# AccelTestJig.net
KiCad netlist of a schematic drawn in EAGLE
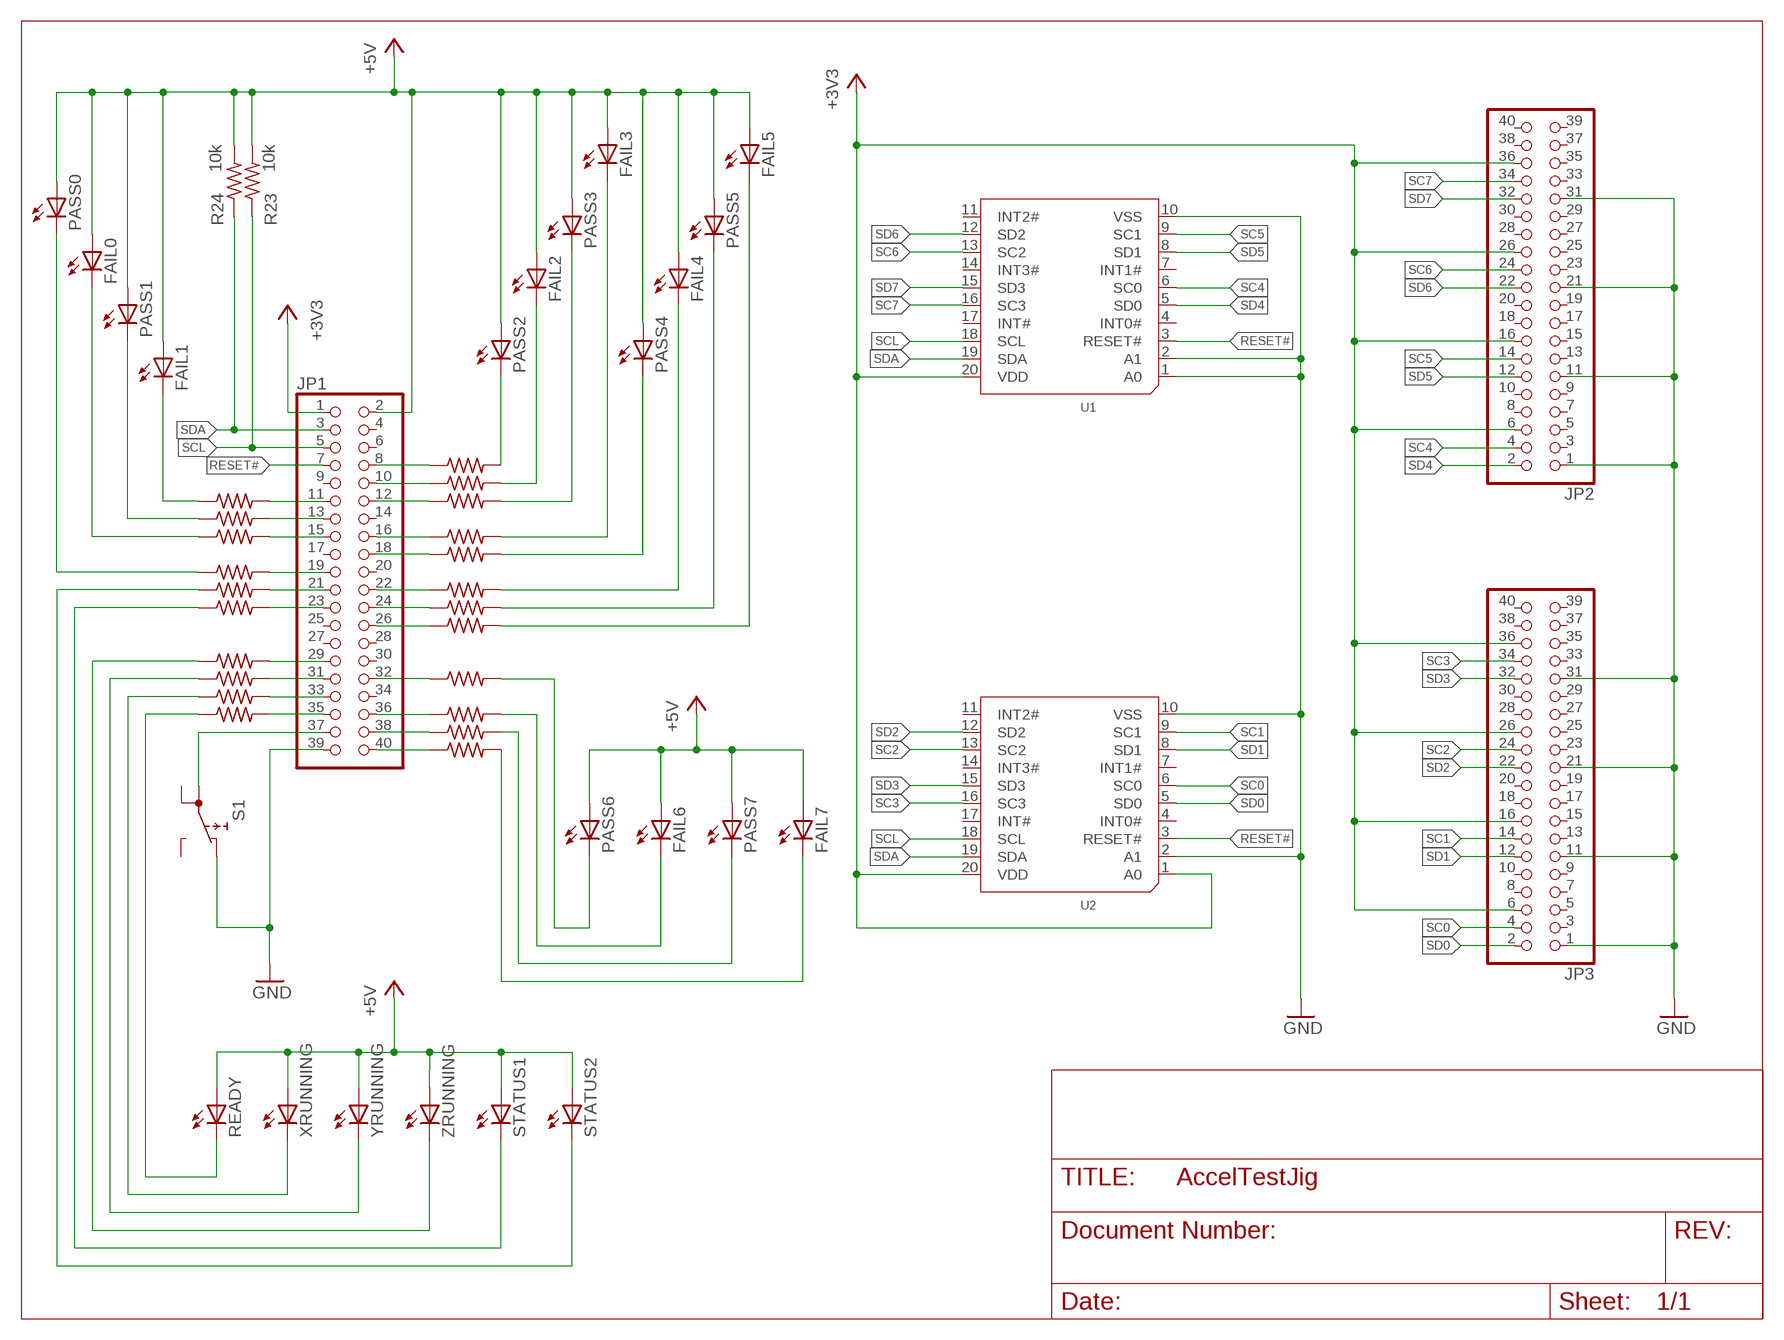
[diagram p0: schematic, sheet 1]

(export (version "E")
  (design (tool "Eeschema 10.0.6"))
  (components
    (comp (ref "FAIL0")
      (value "FAIL")
      (footprint "eagle-import:CHIPLED_0805")
      (libsource (lib "eagle-import") (part "LEDCHIPLED_0805"))
    )
    (comp (ref "FAIL1")
      (value "FAIL")
      (footprint "eagle-import:CHIPLED_0805")
      (libsource (lib "eagle-import") (part "LEDCHIPLED_0805"))
    )
    (comp (ref "FAIL2")
      (value "FAIL")
      (footprint "eagle-import:CHIPLED_0805")
      (libsource (lib "eagle-import") (part "LEDCHIPLED_0805"))
    )
    (comp (ref "FAIL3")
      (value "FAIL")
      (footprint "eagle-import:CHIPLED_0805")
      (libsource (lib "eagle-import") (part "LEDCHIPLED_0805"))
    )
    (comp (ref "FAIL4")
      (value "FAIL")
      (footprint "eagle-import:CHIPLED_0805")
      (libsource (lib "eagle-import") (part "LEDCHIPLED_0805"))
    )
    (comp (ref "FAIL5")
      (value "FAIL")
      (footprint "eagle-import:CHIPLED_0805")
      (libsource (lib "eagle-import") (part "LEDCHIPLED_0805"))
    )
    (comp (ref "FAIL6")
      (value "FAIL")
      (footprint "eagle-import:CHIPLED_0805")
      (libsource (lib "eagle-import") (part "LEDCHIPLED_0805"))
    )
    (comp (ref "FAIL7")
      (value "FAIL")
      (footprint "eagle-import:CHIPLED_0805")
      (libsource (lib "eagle-import") (part "LEDCHIPLED_0805"))
    )
    (comp (ref "JP1")
      (value "NONE")
      (footprint "eagle-import:2X20")
      (libsource (lib "eagle-import") (part "PINHD-2X20"))
    )
    (comp (ref "JP2")
      (value "NONE")
      (footprint "eagle-import:2X20-WIDE")
      (libsource (lib "eagle-import") (part "PINHD(2X20-WIDE)"))
    )
    (comp (ref "JP3")
      (value "NONE")
      (footprint "eagle-import:2X20-WIDE")
      (libsource (lib "eagle-import") (part "PINHD(2X20-WIDE)"))
    )
    (comp (ref "PASS0")
      (value "PASS")
      (footprint "eagle-import:CHIPLED_0805")
      (libsource (lib "eagle-import") (part "LEDCHIPLED_0805"))
    )
    (comp (ref "PASS1")
      (value "PASS")
      (footprint "eagle-import:CHIPLED_0805")
      (libsource (lib "eagle-import") (part "LEDCHIPLED_0805"))
    )
    (comp (ref "PASS2")
      (value "PASS")
      (footprint "eagle-import:CHIPLED_0805")
      (libsource (lib "eagle-import") (part "LEDCHIPLED_0805"))
    )
    (comp (ref "PASS3")
      (value "PASS")
      (footprint "eagle-import:CHIPLED_0805")
      (libsource (lib "eagle-import") (part "LEDCHIPLED_0805"))
    )
    (comp (ref "PASS4")
      (value "PASS")
      (footprint "eagle-import:CHIPLED_0805")
      (libsource (lib "eagle-import") (part "LEDCHIPLED_0805"))
    )
    (comp (ref "PASS5")
      (value "PASS")
      (footprint "eagle-import:CHIPLED_0805")
      (libsource (lib "eagle-import") (part "LEDCHIPLED_0805"))
    )
    (comp (ref "PASS6")
      (value "PASS")
      (footprint "eagle-import:CHIPLED_0805")
      (libsource (lib "eagle-import") (part "LEDCHIPLED_0805"))
    )
    (comp (ref "PASS7")
      (value "PASS")
      (footprint "eagle-import:CHIPLED_0805")
      (libsource (lib "eagle-import") (part "LEDCHIPLED_0805"))
    )
    (comp (ref "R1")
      (value "100")
      (footprint "eagle-import:R0805")
      (libsource (lib "eagle-import") (part "R-US_R0805"))
    )
    (comp (ref "R2")
      (value "100")
      (footprint "eagle-import:R0805")
      (libsource (lib "eagle-import") (part "R-US_R0805"))
    )
    (comp (ref "R3")
      (value "100")
      (footprint "eagle-import:R0805")
      (libsource (lib "eagle-import") (part "R-US_R0805"))
    )
    (comp (ref "R4")
      (value "100")
      (footprint "eagle-import:R0805")
      (libsource (lib "eagle-import") (part "R-US_R0805"))
    )
    (comp (ref "R5")
      (value "100")
      (footprint "eagle-import:R0805")
      (libsource (lib "eagle-import") (part "R-US_R0805"))
    )
    (comp (ref "R6")
      (value "100")
      (footprint "eagle-import:R0805")
      (libsource (lib "eagle-import") (part "R-US_R0805"))
    )
    (comp (ref "R7")
      (value "100")
      (footprint "eagle-import:R0805")
      (libsource (lib "eagle-import") (part "R-US_R0805"))
    )
    (comp (ref "R8")
      (value "100")
      (footprint "eagle-import:R0805")
      (libsource (lib "eagle-import") (part "R-US_R0805"))
    )
    (comp (ref "R9")
      (value "100")
      (footprint "eagle-import:R0805")
      (libsource (lib "eagle-import") (part "R-US_R0805"))
    )
    (comp (ref "R10")
      (value "100")
      (footprint "eagle-import:R0805")
      (libsource (lib "eagle-import") (part "R-US_R0805"))
    )
    (comp (ref "R11")
      (value "100")
      (footprint "eagle-import:R0805")
      (libsource (lib "eagle-import") (part "R-US_R0805"))
    )
    (comp (ref "R12")
      (value "100")
      (footprint "eagle-import:R0805")
      (libsource (lib "eagle-import") (part "R-US_R0805"))
    )
    (comp (ref "R13")
      (value "100")
      (footprint "eagle-import:R0805")
      (libsource (lib "eagle-import") (part "R-US_R0805"))
    )
    (comp (ref "R14")
      (value "100")
      (footprint "eagle-import:R0805")
      (libsource (lib "eagle-import") (part "R-US_R0805"))
    )
    (comp (ref "R15")
      (value "100")
      (footprint "eagle-import:R0805")
      (libsource (lib "eagle-import") (part "R-US_R0805"))
    )
    (comp (ref "R16")
      (value "100")
      (footprint "eagle-import:R0805")
      (libsource (lib "eagle-import") (part "R-US_R0805"))
    )
    (comp (ref "R17")
      (value "100")
      (footprint "eagle-import:R0805")
      (libsource (lib "eagle-import") (part "R-US_R0805"))
    )
    (comp (ref "R18")
      (value "100")
      (footprint "eagle-import:R0805")
      (libsource (lib "eagle-import") (part "R-US_R0805"))
    )
    (comp (ref "R19")
      (value "100")
      (footprint "eagle-import:R0805")
      (libsource (lib "eagle-import") (part "R-US_R0805"))
    )
    (comp (ref "R20")
      (value "100")
      (footprint "eagle-import:R0805")
      (libsource (lib "eagle-import") (part "R-US_R0805"))
    )
    (comp (ref "R21")
      (value "100")
      (footprint "eagle-import:R0805")
      (libsource (lib "eagle-import") (part "R-US_R0805"))
    )
    (comp (ref "R22")
      (value "100")
      (footprint "eagle-import:R0805")
      (libsource (lib "eagle-import") (part "R-US_R0805"))
    )
    (comp (ref "R23")
      (value "10k")
      (footprint "eagle-import:R0805")
      (libsource (lib "eagle-import") (part "R-US_R0805"))
    )
    (comp (ref "R24")
      (value "10k")
      (footprint "eagle-import:R0805")
      (libsource (lib "eagle-import") (part "R-US_R0805"))
    )
    (comp (ref "READY")
      (value "READY")
      (footprint "eagle-import:CHIPLED_0805")
      (libsource (lib "eagle-import") (part "LEDCHIPLED_0805"))
    )
    (comp (ref "S1")
      (value "START")
      (footprint "eagle-import:6X6SMD")
      (libsource (lib "eagle-import") (part "PUSHBUTTON(6X6SMD)01"))
    )
    (comp (ref "STATUS1")
      (value "NONE")
      (footprint "eagle-import:CHIPLED_0805")
      (libsource (lib "eagle-import") (part "LEDCHIPLED_0805"))
    )
    (comp (ref "STATUS2")
      (value "NONE")
      (footprint "eagle-import:CHIPLED_0805")
      (libsource (lib "eagle-import") (part "LEDCHIPLED_0805"))
    )
    (comp (ref "U1")
      (value "NONE")
      (footprint "eagle-import:SOIC20")
      (libsource (lib "eagle-import") (part "PCA9545(SOIC20)"))
    )
    (comp (ref "U2")
      (value "NONE")
      (footprint "eagle-import:SOIC20")
      (libsource (lib "eagle-import") (part "PCA9545(SOIC20)"))
    )
    (comp (ref "XRUNNING")
      (value "TESTING X")
      (footprint "eagle-import:CHIPLED_0805")
      (libsource (lib "eagle-import") (part "LEDCHIPLED_0805"))
    )
    (comp (ref "YRUNNING")
      (value "TESTING Y")
      (footprint "eagle-import:CHIPLED_0805")
      (libsource (lib "eagle-import") (part "LEDCHIPLED_0805"))
    )
    (comp (ref "ZRUNNING")
      (value "TESTING Z")
      (footprint "eagle-import:CHIPLED_0805")
      (libsource (lib "eagle-import") (part "LEDCHIPLED_0805"))
    )
  )
  (nets
    (net (code "1") (name "+3V3") (class "Default")
      (node (ref "JP1") (pin "1") (pinfunction "1_1") (pintype "passive"))
      (node (ref "JP2") (pin "16") (pinfunction "16_16") (pintype "passive"))
      (node (ref "JP2") (pin "26") (pinfunction "26_26") (pintype "passive"))
      (node (ref "JP2") (pin "36") (pinfunction "36_36") (pintype "passive"))
      (node (ref "JP2") (pin "6") (pinfunction "6_6") (pintype "passive"))
      (node (ref "JP3") (pin "16") (pinfunction "16_16") (pintype "passive"))
      (node (ref "JP3") (pin "26") (pinfunction "26_26") (pintype "passive"))
      (node (ref "JP3") (pin "36") (pinfunction "36_36") (pintype "passive"))
      (node (ref "JP3") (pin "6") (pinfunction "6_6") (pintype "passive"))
      (node (ref "U1") (pin "20") (pinfunction "VDD_20") (pintype "bidirectional"))
      (node (ref "U2") (pin "1") (pinfunction "A0_1") (pintype "bidirectional"))
      (node (ref "U2") (pin "20") (pinfunction "VDD_20") (pintype "bidirectional"))
    )
    (net (code "2") (name "+5V") (class "Default")
      (node (ref "FAIL0") (pin "A") (pinfunction "A_A") (pintype "passive"))
      (node (ref "FAIL1") (pin "A") (pinfunction "A_A") (pintype "passive"))
      (node (ref "FAIL2") (pin "A") (pinfunction "A_A") (pintype "passive"))
      (node (ref "FAIL3") (pin "A") (pinfunction "A_A") (pintype "passive"))
      (node (ref "FAIL4") (pin "A") (pinfunction "A_A") (pintype "passive"))
      (node (ref "FAIL5") (pin "A") (pinfunction "A_A") (pintype "passive"))
      (node (ref "FAIL6") (pin "A") (pinfunction "A_A") (pintype "passive"))
      (node (ref "FAIL7") (pin "A") (pinfunction "A_A") (pintype "passive"))
      (node (ref "JP1") (pin "2") (pinfunction "2_2") (pintype "passive"))
      (node (ref "PASS0") (pin "A") (pinfunction "A_A") (pintype "passive"))
      (node (ref "PASS1") (pin "A") (pinfunction "A_A") (pintype "passive"))
      (node (ref "PASS2") (pin "A") (pinfunction "A_A") (pintype "passive"))
      (node (ref "PASS3") (pin "A") (pinfunction "A_A") (pintype "passive"))
      (node (ref "PASS4") (pin "A") (pinfunction "A_A") (pintype "passive"))
      (node (ref "PASS5") (pin "A") (pinfunction "A_A") (pintype "passive"))
      (node (ref "PASS6") (pin "A") (pinfunction "A_A") (pintype "passive"))
      (node (ref "PASS7") (pin "A") (pinfunction "A_A") (pintype "passive"))
      (node (ref "R23") (pin "2") (pinfunction "2_2") (pintype "passive"))
      (node (ref "R24") (pin "2") (pinfunction "2_2") (pintype "passive"))
      (node (ref "READY") (pin "A") (pinfunction "A_A") (pintype "passive"))
      (node (ref "STATUS1") (pin "A") (pinfunction "A_A") (pintype "passive"))
      (node (ref "STATUS2") (pin "A") (pinfunction "A_A") (pintype "passive"))
      (node (ref "XRUNNING") (pin "A") (pinfunction "A_A") (pintype "passive"))
      (node (ref "YRUNNING") (pin "A") (pinfunction "A_A") (pintype "passive"))
      (node (ref "ZRUNNING") (pin "A") (pinfunction "A_A") (pintype "passive"))
    )
    (net (code "3") (name "GND") (class "Default")
      (node (ref "JP1") (pin "39") (pinfunction "39_39") (pintype "passive"))
      (node (ref "JP2") (pin "1") (pinfunction "1_1") (pintype "passive"))
      (node (ref "JP2") (pin "11") (pinfunction "11_11") (pintype "passive"))
      (node (ref "JP2") (pin "21") (pinfunction "21_21") (pintype "passive"))
      (node (ref "JP2") (pin "31") (pinfunction "31_31") (pintype "passive"))
      (node (ref "JP3") (pin "1") (pinfunction "1_1") (pintype "passive"))
      (node (ref "JP3") (pin "11") (pinfunction "11_11") (pintype "passive"))
      (node (ref "JP3") (pin "21") (pinfunction "21_21") (pintype "passive"))
      (node (ref "JP3") (pin "31") (pinfunction "31_31") (pintype "passive"))
      (node (ref "S1") (pin "P$2") (pinfunction "2_P$2") (pintype "passive"))
      (node (ref "U1") (pin "1") (pinfunction "A0_1") (pintype "bidirectional"))
      (node (ref "U1") (pin "10") (pinfunction "VSS_10") (pintype "bidirectional"))
      (node (ref "U1") (pin "2") (pinfunction "A1_2") (pintype "bidirectional"))
      (node (ref "U2") (pin "10") (pinfunction "VSS_10") (pintype "bidirectional"))
      (node (ref "U2") (pin "2") (pinfunction "A1_2") (pintype "bidirectional"))
    )
    (net (code "4") (name "Net-(FAIL0-PadC)") (class "Default")
      (node (ref "FAIL0") (pin "C") (pinfunction "C_C") (pintype "passive"))
      (node (ref "R18") (pin "1") (pinfunction "1_1") (pintype "passive"))
    )
    (net (code "5") (name "Net-(FAIL1-PadC)") (class "Default")
      (node (ref "FAIL1") (pin "C") (pinfunction "C_C") (pintype "passive"))
      (node (ref "R16") (pin "1") (pinfunction "1_1") (pintype "passive"))
    )
    (net (code "6") (name "Net-(FAIL2-PadC)") (class "Default")
      (node (ref "FAIL2") (pin "C") (pinfunction "C_C") (pintype "passive"))
      (node (ref "R2") (pin "2") (pinfunction "2_2") (pintype "passive"))
    )
    (net (code "7") (name "Net-(FAIL3-PadC)") (class "Default")
      (node (ref "FAIL3") (pin "C") (pinfunction "C_C") (pintype "passive"))
      (node (ref "R3") (pin "2") (pinfunction "2_2") (pintype "passive"))
    )
    (net (code "8") (name "Net-(FAIL4-PadC)") (class "Default")
      (node (ref "FAIL4") (pin "C") (pinfunction "C_C") (pintype "passive"))
      (node (ref "R5") (pin "2") (pinfunction "2_2") (pintype "passive"))
    )
    (net (code "9") (name "Net-(FAIL5-PadC)") (class "Default")
      (node (ref "FAIL5") (pin "C") (pinfunction "C_C") (pintype "passive"))
      (node (ref "R7") (pin "2") (pinfunction "2_2") (pintype "passive"))
    )
    (net (code "10") (name "Net-(FAIL6-PadC)") (class "Default")
      (node (ref "FAIL6") (pin "C") (pinfunction "C_C") (pintype "passive"))
      (node (ref "R9") (pin "2") (pinfunction "2_2") (pintype "passive"))
    )
    (net (code "11") (name "Net-(FAIL7-PadC)") (class "Default")
      (node (ref "FAIL7") (pin "C") (pinfunction "C_C") (pintype "passive"))
      (node (ref "R15") (pin "2") (pinfunction "2_2") (pintype "passive"))
    )
    (net (code "12") (name "Net-(JP1-Pad8)") (class "Default")
      (node (ref "JP1") (pin "8") (pinfunction "8_8") (pintype "passive"))
      (node (ref "R1") (pin "1") (pinfunction "1_1") (pintype "passive"))
    )
    (net (code "13") (name "Net-(JP1-Pad10)") (class "Default")
      (node (ref "JP1") (pin "10") (pinfunction "10_10") (pintype "passive"))
      (node (ref "R2") (pin "1") (pinfunction "1_1") (pintype "passive"))
    )
    (net (code "14") (name "Net-(JP1-Pad11)") (class "Default")
      (node (ref "JP1") (pin "11") (pinfunction "11_11") (pintype "passive"))
      (node (ref "R16") (pin "2") (pinfunction "2_2") (pintype "passive"))
    )
    (net (code "15") (name "Net-(JP1-Pad12)") (class "Default")
      (node (ref "JP1") (pin "12") (pinfunction "12_12") (pintype "passive"))
      (node (ref "R14") (pin "1") (pinfunction "1_1") (pintype "passive"))
    )
    (net (code "16") (name "Net-(JP1-Pad13)") (class "Default")
      (node (ref "JP1") (pin "13") (pinfunction "13_13") (pintype "passive"))
      (node (ref "R17") (pin "2") (pinfunction "2_2") (pintype "passive"))
    )
    (net (code "17") (name "Net-(JP1-Pad15)") (class "Default")
      (node (ref "JP1") (pin "15") (pinfunction "15_15") (pintype "passive"))
      (node (ref "R18") (pin "2") (pinfunction "2_2") (pintype "passive"))
    )
    (net (code "18") (name "Net-(JP1-Pad16)") (class "Default")
      (node (ref "JP1") (pin "16") (pinfunction "16_16") (pintype "passive"))
      (node (ref "R3") (pin "1") (pinfunction "1_1") (pintype "passive"))
    )
    (net (code "19") (name "Net-(JP1-Pad18)") (class "Default")
      (node (ref "JP1") (pin "18") (pinfunction "18_18") (pintype "passive"))
      (node (ref "R4") (pin "1") (pinfunction "1_1") (pintype "passive"))
    )
    (net (code "20") (name "Net-(JP1-Pad19)") (class "Default")
      (node (ref "JP1") (pin "19") (pinfunction "19_19") (pintype "passive"))
      (node (ref "R19") (pin "2") (pinfunction "2_2") (pintype "passive"))
    )
    (net (code "21") (name "Net-(JP1-Pad21)") (class "Default")
      (node (ref "JP1") (pin "21") (pinfunction "21_21") (pintype "passive"))
      (node (ref "R20") (pin "2") (pinfunction "2_2") (pintype "passive"))
    )
    (net (code "22") (name "Net-(JP1-Pad22)") (class "Default")
      (node (ref "JP1") (pin "22") (pinfunction "22_22") (pintype "passive"))
      (node (ref "R5") (pin "1") (pinfunction "1_1") (pintype "passive"))
    )
    (net (code "23") (name "Net-(JP1-Pad23)") (class "Default")
      (node (ref "JP1") (pin "23") (pinfunction "23_23") (pintype "passive"))
      (node (ref "R11") (pin "2") (pinfunction "2_2") (pintype "passive"))
    )
    (net (code "24") (name "Net-(JP1-Pad24)") (class "Default")
      (node (ref "JP1") (pin "24") (pinfunction "24_24") (pintype "passive"))
      (node (ref "R6") (pin "1") (pinfunction "1_1") (pintype "passive"))
    )
    (net (code "25") (name "Net-(JP1-Pad26)") (class "Default")
      (node (ref "JP1") (pin "26") (pinfunction "26_26") (pintype "passive"))
      (node (ref "R7") (pin "1") (pinfunction "1_1") (pintype "passive"))
    )
    (net (code "26") (name "Net-(JP1-Pad29)") (class "Default")
      (node (ref "JP1") (pin "29") (pinfunction "29_29") (pintype "passive"))
      (node (ref "R12") (pin "2") (pinfunction "2_2") (pintype "passive"))
    )
    (net (code "27") (name "Net-(JP1-Pad31)") (class "Default")
      (node (ref "JP1") (pin "31") (pinfunction "31_31") (pintype "passive"))
      (node (ref "R13") (pin "2") (pinfunction "2_2") (pintype "passive"))
    )
    (net (code "28") (name "Net-(JP1-Pad32)") (class "Default")
      (node (ref "JP1") (pin "32") (pinfunction "32_32") (pintype "passive"))
      (node (ref "R8") (pin "1") (pinfunction "1_1") (pintype "passive"))
    )
    (net (code "29") (name "Net-(JP1-Pad33)") (class "Default")
      (node (ref "JP1") (pin "33") (pinfunction "33_33") (pintype "passive"))
      (node (ref "R21") (pin "2") (pinfunction "2_2") (pintype "passive"))
    )
    (net (code "30") (name "Net-(JP1-Pad35)") (class "Default")
      (node (ref "JP1") (pin "35") (pinfunction "35_35") (pintype "passive"))
      (node (ref "R22") (pin "2") (pinfunction "2_2") (pintype "passive"))
    )
    (net (code "31") (name "Net-(JP1-Pad36)") (class "Default")
      (node (ref "JP1") (pin "36") (pinfunction "36_36") (pintype "passive"))
      (node (ref "R9") (pin "1") (pinfunction "1_1") (pintype "passive"))
    )
    (net (code "32") (name "Net-(JP1-Pad38)") (class "Default")
      (node (ref "JP1") (pin "38") (pinfunction "38_38") (pintype "passive"))
      (node (ref "R10") (pin "1") (pinfunction "1_1") (pintype "passive"))
    )
    (net (code "33") (name "Net-(JP1-Pad40)") (class "Default")
      (node (ref "JP1") (pin "40") (pinfunction "40_40") (pintype "passive"))
      (node (ref "R15") (pin "1") (pinfunction "1_1") (pintype "passive"))
    )
    (net (code "34") (name "Net-(PASS0-PadC)") (class "Default")
      (node (ref "PASS0") (pin "C") (pinfunction "C_C") (pintype "passive"))
      (node (ref "R19") (pin "1") (pinfunction "1_1") (pintype "passive"))
    )
    (net (code "35") (name "Net-(PASS1-PadC)") (class "Default")
      (node (ref "PASS1") (pin "C") (pinfunction "C_C") (pintype "passive"))
      (node (ref "R17") (pin "1") (pinfunction "1_1") (pintype "passive"))
    )
    (net (code "36") (name "Net-(PASS2-PadC)") (class "Default")
      (node (ref "PASS2") (pin "C") (pinfunction "C_C") (pintype "passive"))
      (node (ref "R1") (pin "2") (pinfunction "2_2") (pintype "passive"))
    )
    (net (code "37") (name "Net-(PASS3-PadC)") (class "Default")
      (node (ref "PASS3") (pin "C") (pinfunction "C_C") (pintype "passive"))
      (node (ref "R14") (pin "2") (pinfunction "2_2") (pintype "passive"))
    )
    (net (code "38") (name "Net-(PASS4-PadC)") (class "Default")
      (node (ref "PASS4") (pin "C") (pinfunction "C_C") (pintype "passive"))
      (node (ref "R4") (pin "2") (pinfunction "2_2") (pintype "passive"))
    )
    (net (code "39") (name "Net-(PASS5-PadC)") (class "Default")
      (node (ref "PASS5") (pin "C") (pinfunction "C_C") (pintype "passive"))
      (node (ref "R6") (pin "2") (pinfunction "2_2") (pintype "passive"))
    )
    (net (code "40") (name "Net-(PASS6-PadC)") (class "Default")
      (node (ref "PASS6") (pin "C") (pinfunction "C_C") (pintype "passive"))
      (node (ref "R8") (pin "2") (pinfunction "2_2") (pintype "passive"))
    )
    (net (code "41") (name "Net-(PASS7-PadC)") (class "Default")
      (node (ref "PASS7") (pin "C") (pinfunction "C_C") (pintype "passive"))
      (node (ref "R10") (pin "2") (pinfunction "2_2") (pintype "passive"))
    )
    (net (code "42") (name "Net-(R11-Pad1)") (class "Default")
      (node (ref "R11") (pin "1") (pinfunction "1_1") (pintype "passive"))
      (node (ref "STATUS1") (pin "C") (pinfunction "C_C") (pintype "passive"))
    )
    (net (code "43") (name "Net-(R12-Pad1)") (class "Default")
      (node (ref "R12") (pin "1") (pinfunction "1_1") (pintype "passive"))
      (node (ref "ZRUNNING") (pin "C") (pinfunction "C_C") (pintype "passive"))
    )
    (net (code "44") (name "Net-(R13-Pad1)") (class "Default")
      (node (ref "R13") (pin "1") (pinfunction "1_1") (pintype "passive"))
      (node (ref "YRUNNING") (pin "C") (pinfunction "C_C") (pintype "passive"))
    )
    (net (code "45") (name "Net-(R20-Pad1)") (class "Default")
      (node (ref "R20") (pin "1") (pinfunction "1_1") (pintype "passive"))
      (node (ref "STATUS2") (pin "C") (pinfunction "C_C") (pintype "passive"))
    )
    (net (code "46") (name "Net-(R21-Pad1)") (class "Default")
      (node (ref "R21") (pin "1") (pinfunction "1_1") (pintype "passive"))
      (node (ref "XRUNNING") (pin "C") (pinfunction "C_C") (pintype "passive"))
    )
    (net (code "47") (name "Net-(R22-Pad1)") (class "Default")
      (node (ref "R22") (pin "1") (pinfunction "1_1") (pintype "passive"))
      (node (ref "READY") (pin "C") (pinfunction "C_C") (pintype "passive"))
    )
    (net (code "48") (name "Net-(S1-1)") (class "Default")
      (node (ref "JP1") (pin "37") (pinfunction "37_37") (pintype "passive"))
      (node (ref "S1") (pin "P$1") (pinfunction "1_P$1") (pintype "passive"))
    )
    (net (code "49") (name "RESET#") (class "Default")
      (node (ref "JP1") (pin "7") (pinfunction "7_7") (pintype "passive"))
      (node (ref "U1") (pin "3") (pinfunction "RESET#_3") (pintype "bidirectional"))
      (node (ref "U2") (pin "3") (pinfunction "RESET#_3") (pintype "bidirectional"))
    )
    (net (code "50") (name "SC0") (class "Default")
      (node (ref "JP3") (pin "4") (pinfunction "4_4") (pintype "passive"))
      (node (ref "U2") (pin "6") (pinfunction "SC0_6") (pintype "bidirectional"))
    )
    (net (code "51") (name "SC1") (class "Default")
      (node (ref "JP3") (pin "14") (pinfunction "14_14") (pintype "passive"))
      (node (ref "U2") (pin "9") (pinfunction "SC1_9") (pintype "bidirectional"))
    )
    (net (code "52") (name "SC2") (class "Default")
      (node (ref "JP3") (pin "24") (pinfunction "24_24") (pintype "passive"))
      (node (ref "U2") (pin "13") (pinfunction "SC2_13") (pintype "bidirectional"))
    )
    (net (code "53") (name "SC3") (class "Default")
      (node (ref "JP3") (pin "34") (pinfunction "34_34") (pintype "passive"))
      (node (ref "U2") (pin "16") (pinfunction "SC3_16") (pintype "bidirectional"))
    )
    (net (code "54") (name "SC4") (class "Default")
      (node (ref "JP2") (pin "4") (pinfunction "4_4") (pintype "passive"))
      (node (ref "U1") (pin "6") (pinfunction "SC0_6") (pintype "bidirectional"))
    )
    (net (code "55") (name "SC5") (class "Default")
      (node (ref "JP2") (pin "14") (pinfunction "14_14") (pintype "passive"))
      (node (ref "U1") (pin "9") (pinfunction "SC1_9") (pintype "bidirectional"))
    )
    (net (code "56") (name "SC6") (class "Default")
      (node (ref "JP2") (pin "24") (pinfunction "24_24") (pintype "passive"))
      (node (ref "U1") (pin "13") (pinfunction "SC2_13") (pintype "bidirectional"))
    )
    (net (code "57") (name "SC7") (class "Default")
      (node (ref "JP2") (pin "34") (pinfunction "34_34") (pintype "passive"))
      (node (ref "U1") (pin "16") (pinfunction "SC3_16") (pintype "bidirectional"))
    )
    (net (code "58") (name "SCL") (class "Default")
      (node (ref "JP1") (pin "5") (pinfunction "5_5") (pintype "passive"))
      (node (ref "R23") (pin "1") (pinfunction "1_1") (pintype "passive"))
      (node (ref "U1") (pin "18") (pinfunction "SCL_18") (pintype "bidirectional"))
      (node (ref "U2") (pin "18") (pinfunction "SCL_18") (pintype "bidirectional"))
    )
    (net (code "59") (name "SD0") (class "Default")
      (node (ref "JP3") (pin "2") (pinfunction "2_2") (pintype "passive"))
      (node (ref "U2") (pin "5") (pinfunction "SD0_5") (pintype "bidirectional"))
    )
    (net (code "60") (name "SD1") (class "Default")
      (node (ref "JP3") (pin "12") (pinfunction "12_12") (pintype "passive"))
      (node (ref "U2") (pin "8") (pinfunction "SD1_8") (pintype "bidirectional"))
    )
    (net (code "61") (name "SD2") (class "Default")
      (node (ref "JP3") (pin "22") (pinfunction "22_22") (pintype "passive"))
      (node (ref "U2") (pin "12") (pinfunction "SD2_12") (pintype "bidirectional"))
    )
    (net (code "62") (name "SD3") (class "Default")
      (node (ref "JP3") (pin "32") (pinfunction "32_32") (pintype "passive"))
      (node (ref "U2") (pin "15") (pinfunction "SD3_15") (pintype "bidirectional"))
    )
    (net (code "63") (name "SD4") (class "Default")
      (node (ref "JP2") (pin "2") (pinfunction "2_2") (pintype "passive"))
      (node (ref "U1") (pin "5") (pinfunction "SD0_5") (pintype "bidirectional"))
    )
    (net (code "64") (name "SD5") (class "Default")
      (node (ref "JP2") (pin "12") (pinfunction "12_12") (pintype "passive"))
      (node (ref "U1") (pin "8") (pinfunction "SD1_8") (pintype "bidirectional"))
    )
    (net (code "65") (name "SD6") (class "Default")
      (node (ref "JP2") (pin "22") (pinfunction "22_22") (pintype "passive"))
      (node (ref "U1") (pin "12") (pinfunction "SD2_12") (pintype "bidirectional"))
    )
    (net (code "66") (name "SD7") (class "Default")
      (node (ref "JP2") (pin "32") (pinfunction "32_32") (pintype "passive"))
      (node (ref "U1") (pin "15") (pinfunction "SD3_15") (pintype "bidirectional"))
    )
    (net (code "67") (name "SDA") (class "Default")
      (node (ref "JP1") (pin "3") (pinfunction "3_3") (pintype "passive"))
      (node (ref "R24") (pin "1") (pinfunction "1_1") (pintype "passive"))
      (node (ref "U1") (pin "19") (pinfunction "SDA_19") (pintype "bidirectional"))
      (node (ref "U2") (pin "19") (pinfunction "SDA_19") (pintype "bidirectional"))
    )
    (net (code "68") (name "unconnected-(JP1-Pad4)") (class "Default")
      (node (ref "JP1") (pin "4") (pinfunction "4_4") (pintype "passive"))
    )
    (net (code "69") (name "unconnected-(JP1-Pad6)") (class "Default")
      (node (ref "JP1") (pin "6") (pinfunction "6_6") (pintype "passive"))
    )
    (net (code "70") (name "unconnected-(JP1-Pad9)") (class "Default")
      (node (ref "JP1") (pin "9") (pinfunction "9_9") (pintype "passive"))
    )
    (net (code "71") (name "unconnected-(JP1-Pad14)") (class "Default")
      (node (ref "JP1") (pin "14") (pinfunction "14_14") (pintype "passive"))
    )
    (net (code "72") (name "unconnected-(JP1-Pad17)") (class "Default")
      (node (ref "JP1") (pin "17") (pinfunction "17_17") (pintype "passive"))
    )
    (net (code "73") (name "unconnected-(JP1-Pad20)") (class "Default")
      (node (ref "JP1") (pin "20") (pinfunction "20_20") (pintype "passive"))
    )
    (net (code "74") (name "unconnected-(JP1-Pad25)") (class "Default")
      (node (ref "JP1") (pin "25") (pinfunction "25_25") (pintype "passive"))
    )
    (net (code "75") (name "unconnected-(JP1-Pad27)") (class "Default")
      (node (ref "JP1") (pin "27") (pinfunction "27_27") (pintype "passive"))
    )
    (net (code "76") (name "unconnected-(JP1-Pad28)") (class "Default")
      (node (ref "JP1") (pin "28") (pinfunction "28_28") (pintype "passive"))
    )
    (net (code "77") (name "unconnected-(JP1-Pad30)") (class "Default")
      (node (ref "JP1") (pin "30") (pinfunction "30_30") (pintype "passive"))
    )
    (net (code "78") (name "unconnected-(JP1-Pad34)") (class "Default")
      (node (ref "JP1") (pin "34") (pinfunction "34_34") (pintype "passive"))
    )
    (net (code "79") (name "unconnected-(JP2-Pad3)") (class "Default")
      (node (ref "JP2") (pin "3") (pinfunction "3_3") (pintype "passive"))
    )
    (net (code "80") (name "unconnected-(JP2-Pad5)") (class "Default")
      (node (ref "JP2") (pin "5") (pinfunction "5_5") (pintype "passive"))
    )
    (net (code "81") (name "unconnected-(JP2-Pad7)") (class "Default")
      (node (ref "JP2") (pin "7") (pinfunction "7_7") (pintype "passive"))
    )
    (net (code "82") (name "unconnected-(JP2-Pad8)") (class "Default")
      (node (ref "JP2") (pin "8") (pinfunction "8_8") (pintype "passive"))
    )
    (net (code "83") (name "unconnected-(JP2-Pad9)") (class "Default")
      (node (ref "JP2") (pin "9") (pinfunction "9_9") (pintype "passive"))
    )
    (net (code "84") (name "unconnected-(JP2-Pad10)") (class "Default")
      (node (ref "JP2") (pin "10") (pinfunction "10_10") (pintype "passive"))
    )
    (net (code "85") (name "unconnected-(JP2-Pad13)") (class "Default")
      (node (ref "JP2") (pin "13") (pinfunction "13_13") (pintype "passive"))
    )
    (net (code "86") (name "unconnected-(JP2-Pad15)") (class "Default")
      (node (ref "JP2") (pin "15") (pinfunction "15_15") (pintype "passive"))
    )
    (net (code "87") (name "unconnected-(JP2-Pad17)") (class "Default")
      (node (ref "JP2") (pin "17") (pinfunction "17_17") (pintype "passive"))
    )
    (net (code "88") (name "unconnected-(JP2-Pad18)") (class "Default")
      (node (ref "JP2") (pin "18") (pinfunction "18_18") (pintype "passive"))
    )
    (net (code "89") (name "unconnected-(JP2-Pad19)") (class "Default")
      (node (ref "JP2") (pin "19") (pinfunction "19_19") (pintype "passive"))
    )
    (net (code "90") (name "unconnected-(JP2-Pad20)") (class "Default")
      (node (ref "JP2") (pin "20") (pinfunction "20_20") (pintype "passive"))
    )
    (net (code "91") (name "unconnected-(JP2-Pad23)") (class "Default")
      (node (ref "JP2") (pin "23") (pinfunction "23_23") (pintype "passive"))
    )
    (net (code "92") (name "unconnected-(JP2-Pad25)") (class "Default")
      (node (ref "JP2") (pin "25") (pinfunction "25_25") (pintype "passive"))
    )
    (net (code "93") (name "unconnected-(JP2-Pad27)") (class "Default")
      (node (ref "JP2") (pin "27") (pinfunction "27_27") (pintype "passive"))
    )
    (net (code "94") (name "unconnected-(JP2-Pad28)") (class "Default")
      (node (ref "JP2") (pin "28") (pinfunction "28_28") (pintype "passive"))
    )
    (net (code "95") (name "unconnected-(JP2-Pad29)") (class "Default")
      (node (ref "JP2") (pin "29") (pinfunction "29_29") (pintype "passive"))
    )
    (net (code "96") (name "unconnected-(JP2-Pad30)") (class "Default")
      (node (ref "JP2") (pin "30") (pinfunction "30_30") (pintype "passive"))
    )
    (net (code "97") (name "unconnected-(JP2-Pad33)") (class "Default")
      (node (ref "JP2") (pin "33") (pinfunction "33_33") (pintype "passive"))
    )
    (net (code "98") (name "unconnected-(JP2-Pad35)") (class "Default")
      (node (ref "JP2") (pin "35") (pinfunction "35_35") (pintype "passive"))
    )
    (net (code "99") (name "unconnected-(JP2-Pad37)") (class "Default")
      (node (ref "JP2") (pin "37") (pinfunction "37_37") (pintype "passive"))
    )
    (net (code "100") (name "unconnected-(JP2-Pad38)") (class "Default")
      (node (ref "JP2") (pin "38") (pinfunction "38_38") (pintype "passive"))
    )
    (net (code "101") (name "unconnected-(JP2-Pad39)") (class "Default")
      (node (ref "JP2") (pin "39") (pinfunction "39_39") (pintype "passive"))
    )
    (net (code "102") (name "unconnected-(JP2-Pad40)") (class "Default")
      (node (ref "JP2") (pin "40") (pinfunction "40_40") (pintype "passive"))
    )
    (net (code "103") (name "unconnected-(JP3-Pad3)") (class "Default")
      (node (ref "JP3") (pin "3") (pinfunction "3_3") (pintype "passive"))
    )
    (net (code "104") (name "unconnected-(JP3-Pad5)") (class "Default")
      (node (ref "JP3") (pin "5") (pinfunction "5_5") (pintype "passive"))
    )
    (net (code "105") (name "unconnected-(JP3-Pad7)") (class "Default")
      (node (ref "JP3") (pin "7") (pinfunction "7_7") (pintype "passive"))
    )
    (net (code "106") (name "unconnected-(JP3-Pad8)") (class "Default")
      (node (ref "JP3") (pin "8") (pinfunction "8_8") (pintype "passive"))
    )
    (net (code "107") (name "unconnected-(JP3-Pad9)") (class "Default")
      (node (ref "JP3") (pin "9") (pinfunction "9_9") (pintype "passive"))
    )
    (net (code "108") (name "unconnected-(JP3-Pad10)") (class "Default")
      (node (ref "JP3") (pin "10") (pinfunction "10_10") (pintype "passive"))
    )
    (net (code "109") (name "unconnected-(JP3-Pad13)") (class "Default")
      (node (ref "JP3") (pin "13") (pinfunction "13_13") (pintype "passive"))
    )
    (net (code "110") (name "unconnected-(JP3-Pad15)") (class "Default")
      (node (ref "JP3") (pin "15") (pinfunction "15_15") (pintype "passive"))
    )
    (net (code "111") (name "unconnected-(JP3-Pad17)") (class "Default")
      (node (ref "JP3") (pin "17") (pinfunction "17_17") (pintype "passive"))
    )
    (net (code "112") (name "unconnected-(JP3-Pad18)") (class "Default")
      (node (ref "JP3") (pin "18") (pinfunction "18_18") (pintype "passive"))
    )
    (net (code "113") (name "unconnected-(JP3-Pad19)") (class "Default")
      (node (ref "JP3") (pin "19") (pinfunction "19_19") (pintype "passive"))
    )
    (net (code "114") (name "unconnected-(JP3-Pad20)") (class "Default")
      (node (ref "JP3") (pin "20") (pinfunction "20_20") (pintype "passive"))
    )
    (net (code "115") (name "unconnected-(JP3-Pad23)") (class "Default")
      (node (ref "JP3") (pin "23") (pinfunction "23_23") (pintype "passive"))
    )
    (net (code "116") (name "unconnected-(JP3-Pad25)") (class "Default")
      (node (ref "JP3") (pin "25") (pinfunction "25_25") (pintype "passive"))
    )
    (net (code "117") (name "unconnected-(JP3-Pad27)") (class "Default")
      (node (ref "JP3") (pin "27") (pinfunction "27_27") (pintype "passive"))
    )
    (net (code "118") (name "unconnected-(JP3-Pad28)") (class "Default")
      (node (ref "JP3") (pin "28") (pinfunction "28_28") (pintype "passive"))
    )
    (net (code "119") (name "unconnected-(JP3-Pad29)") (class "Default")
      (node (ref "JP3") (pin "29") (pinfunction "29_29") (pintype "passive"))
    )
    (net (code "120") (name "unconnected-(JP3-Pad30)") (class "Default")
      (node (ref "JP3") (pin "30") (pinfunction "30_30") (pintype "passive"))
    )
    (net (code "121") (name "unconnected-(JP3-Pad33)") (class "Default")
      (node (ref "JP3") (pin "33") (pinfunction "33_33") (pintype "passive"))
    )
    (net (code "122") (name "unconnected-(JP3-Pad35)") (class "Default")
      (node (ref "JP3") (pin "35") (pinfunction "35_35") (pintype "passive"))
    )
    (net (code "123") (name "unconnected-(JP3-Pad37)") (class "Default")
      (node (ref "JP3") (pin "37") (pinfunction "37_37") (pintype "passive"))
    )
    (net (code "124") (name "unconnected-(JP3-Pad38)") (class "Default")
      (node (ref "JP3") (pin "38") (pinfunction "38_38") (pintype "passive"))
    )
    (net (code "125") (name "unconnected-(JP3-Pad39)") (class "Default")
      (node (ref "JP3") (pin "39") (pinfunction "39_39") (pintype "passive"))
    )
    (net (code "126") (name "unconnected-(JP3-Pad40)") (class "Default")
      (node (ref "JP3") (pin "40") (pinfunction "40_40") (pintype "passive"))
    )
    (net (code "127") (name "unconnected-(S1-3-PadP$3)") (class "Default")
      (node (ref "S1") (pin "P$3") (pinfunction "3_P$3") (pintype "passive"))
    )
    (net (code "128") (name "unconnected-(S1-4-PadP$4)") (class "Default")
      (node (ref "S1") (pin "P$4") (pinfunction "4_P$4") (pintype "passive"))
    )
    (net (code "129") (name "unconnected-(U1-INT#-Pad17)") (class "Default")
      (node (ref "U1") (pin "17") (pinfunction "INT#_17") (pintype "bidirectional"))
    )
    (net (code "130") (name "unconnected-(U1-INT0#-Pad4)") (class "Default")
      (node (ref "U1") (pin "4") (pinfunction "INT0#_4") (pintype "bidirectional"))
    )
    (net (code "131") (name "unconnected-(U1-INT1#-Pad7)") (class "Default")
      (node (ref "U1") (pin "7") (pinfunction "INT1#_7") (pintype "bidirectional"))
    )
    (net (code "132") (name "unconnected-(U1-INT2#-Pad11)") (class "Default")
      (node (ref "U1") (pin "11") (pinfunction "INT2#_11") (pintype "bidirectional"))
    )
    (net (code "133") (name "unconnected-(U1-INT3#-Pad14)") (class "Default")
      (node (ref "U1") (pin "14") (pinfunction "INT3#_14") (pintype "bidirectional"))
    )
    (net (code "134") (name "unconnected-(U2-INT#-Pad17)") (class "Default")
      (node (ref "U2") (pin "17") (pinfunction "INT#_17") (pintype "bidirectional"))
    )
    (net (code "135") (name "unconnected-(U2-INT0#-Pad4)") (class "Default")
      (node (ref "U2") (pin "4") (pinfunction "INT0#_4") (pintype "bidirectional"))
    )
    (net (code "136") (name "unconnected-(U2-INT1#-Pad7)") (class "Default")
      (node (ref "U2") (pin "7") (pinfunction "INT1#_7") (pintype "bidirectional"))
    )
    (net (code "137") (name "unconnected-(U2-INT2#-Pad11)") (class "Default")
      (node (ref "U2") (pin "11") (pinfunction "INT2#_11") (pintype "bidirectional"))
    )
    (net (code "138") (name "unconnected-(U2-INT3#-Pad14)") (class "Default")
      (node (ref "U2") (pin "14") (pinfunction "INT3#_14") (pintype "bidirectional"))
    )
  )
)
